# FX-Flash_PLCC_rev_C.net
KiCad netlist of a schematic drawn in EAGLE
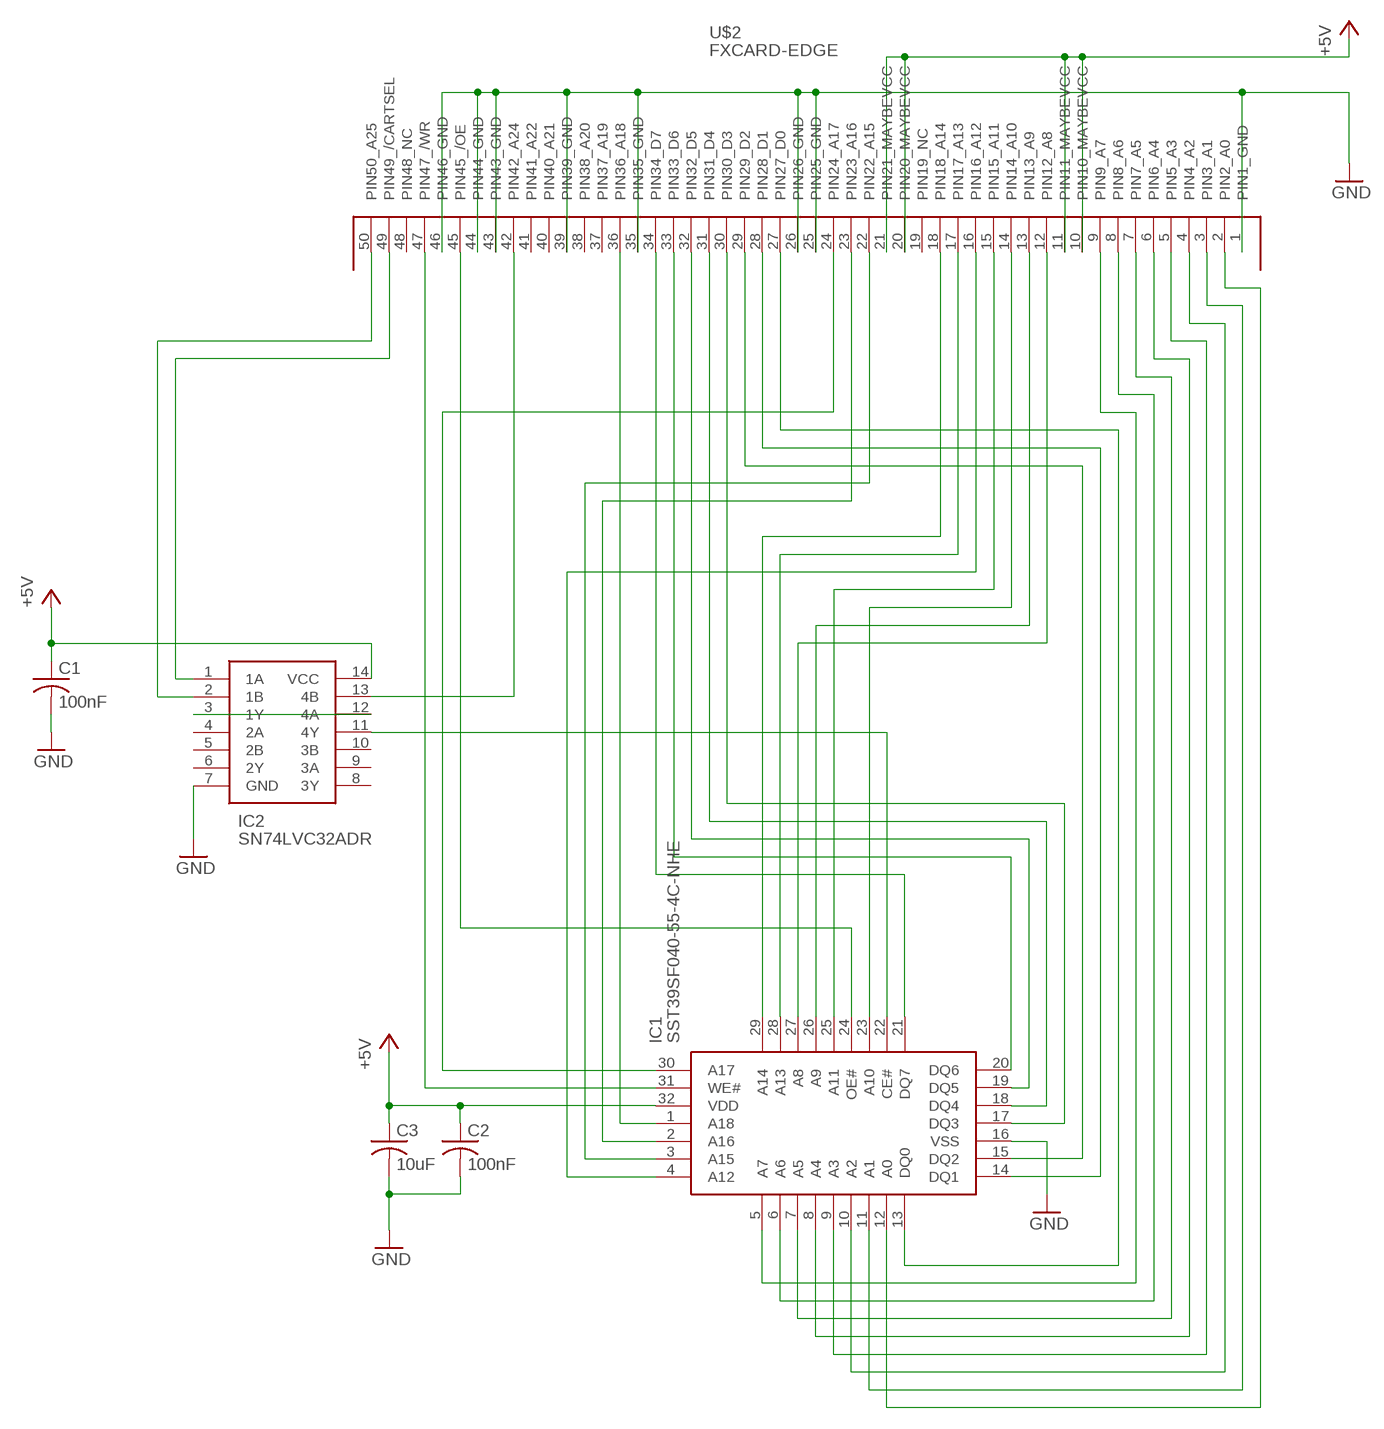
[diagram p0: schematic, sheet 1]

(export (version "E")
  (design (tool "Eeschema 10.0.6"))
  (components
    (comp (ref "C1")
      (value "100nF")
      (footprint "eagle-import:C0805")
      (libsource (lib "eagle-import") (part "C-USC0805"))
    )
    (comp (ref "C2")
      (value "100nF")
      (footprint "eagle-import:C0805")
      (libsource (lib "eagle-import") (part "C-USC0805"))
    )
    (comp (ref "C3")
      (value "10uF")
      (footprint "eagle-import:C0805")
      (libsource (lib "eagle-import") (part "C-USC0805"))
    )
    (comp (ref "IC1")
      (value "SST39SF040-55-4C-NHE")
      (footprint "eagle-import:PLCC127P1245X1499X356-32N")
      (fields (field (name "MOUSER_PART_NUMBER") "579-39SF0405CNHE"))
      (libsource (lib "eagle-import") (part "SST39SF040-55-4C-NHE"))
    )
    (comp (ref "IC2")
      (value "SN74LVC32ADR")
      (footprint "eagle-import:SOIC127P600X175-14N")
      (fields (field (name "MOUSER_PART_NUMBER") "595-SN74LVC32ADR"))
      (libsource (lib "eagle-import") (part "SN74LVC32ADR"))
    )
    (comp (ref "U$2")
      (value "FXCARD-EDGE")
      (footprint "eagle-import:FXCARD-EDGE")
      (libsource (lib "eagle-import") (part "FXCARD-EDGE"))
    )
  )
  (nets
    (net (code "1") (name "+5V") (class "Default")
      (node (ref "C1") (pin "1") (pinfunction "1_1") (pintype "passive"))
      (node (ref "C2") (pin "1") (pinfunction "1_1") (pintype "passive"))
      (node (ref "C3") (pin "1") (pinfunction "1_1") (pintype "passive"))
      (node (ref "IC1") (pin "32") (pinfunction "VDD_32") (pintype "bidirectional"))
      (node (ref "IC2") (pin "14") (pinfunction "VCC_14") (pintype "bidirectional"))
      (node (ref "U$2") (pin "10") (pinfunction "PIN10_MAYBEVCC_10") (pintype "bidirectional"))
      (node (ref "U$2") (pin "11") (pinfunction "PIN11_MAYBEVCC_11") (pintype "bidirectional"))
      (node (ref "U$2") (pin "20") (pinfunction "PIN20_MAYBEVCC_20") (pintype "bidirectional"))
      (node (ref "U$2") (pin "21") (pinfunction "PIN21_MAYBEVCC_21") (pintype "bidirectional"))
    )
    (net (code "2") (name "GND") (class "Default")
      (node (ref "C1") (pin "2") (pinfunction "2_2") (pintype "passive"))
      (node (ref "C2") (pin "2") (pinfunction "2_2") (pintype "passive"))
      (node (ref "C3") (pin "2") (pinfunction "2_2") (pintype "passive"))
      (node (ref "IC1") (pin "16") (pinfunction "VSS_16") (pintype "bidirectional"))
      (node (ref "IC2") (pin "7") (pinfunction "GND_7") (pintype "bidirectional"))
      (node (ref "U$2") (pin "1") (pinfunction "PIN1_GND_1") (pintype "power_in"))
      (node (ref "U$2") (pin "25") (pinfunction "PIN25_GND_25") (pintype "power_in"))
      (node (ref "U$2") (pin "26") (pinfunction "PIN26_GND_26") (pintype "power_in"))
      (node (ref "U$2") (pin "35") (pinfunction "PIN35_GND_35") (pintype "power_in"))
      (node (ref "U$2") (pin "39") (pinfunction "PIN39_GND_39") (pintype "power_in"))
      (node (ref "U$2") (pin "43") (pinfunction "PIN43_GND_43") (pintype "power_in"))
      (node (ref "U$2") (pin "44") (pinfunction "PIN44_GND_44") (pintype "power_in"))
      (node (ref "U$2") (pin "46") (pinfunction "PIN46_GND_46") (pintype "power_in"))
    )
    (net (code "3") (name "Net-(IC1-A0)") (class "Default")
      (node (ref "IC1") (pin "12") (pinfunction "A0_12") (pintype "bidirectional"))
      (node (ref "U$2") (pin "2") (pinfunction "PIN2_A0_2") (pintype "bidirectional"))
    )
    (net (code "4") (name "Net-(IC1-A1)") (class "Default")
      (node (ref "IC1") (pin "11") (pinfunction "A1_11") (pintype "bidirectional"))
      (node (ref "U$2") (pin "3") (pinfunction "PIN3_A1_3") (pintype "bidirectional"))
    )
    (net (code "5") (name "Net-(IC1-A2)") (class "Default")
      (node (ref "IC1") (pin "10") (pinfunction "A2_10") (pintype "bidirectional"))
      (node (ref "U$2") (pin "4") (pinfunction "PIN4_A2_4") (pintype "bidirectional"))
    )
    (net (code "6") (name "Net-(IC1-A3)") (class "Default")
      (node (ref "IC1") (pin "9") (pinfunction "A3_9") (pintype "bidirectional"))
      (node (ref "U$2") (pin "5") (pinfunction "PIN5_A3_5") (pintype "bidirectional"))
    )
    (net (code "7") (name "Net-(IC1-A4)") (class "Default")
      (node (ref "IC1") (pin "8") (pinfunction "A4_8") (pintype "bidirectional"))
      (node (ref "U$2") (pin "6") (pinfunction "PIN6_A4_6") (pintype "bidirectional"))
    )
    (net (code "8") (name "Net-(IC1-A5)") (class "Default")
      (node (ref "IC1") (pin "7") (pinfunction "A5_7") (pintype "bidirectional"))
      (node (ref "U$2") (pin "7") (pinfunction "PIN7_A5_7") (pintype "bidirectional"))
    )
    (net (code "9") (name "Net-(IC1-A6)") (class "Default")
      (node (ref "IC1") (pin "6") (pinfunction "A6_6") (pintype "bidirectional"))
      (node (ref "U$2") (pin "8") (pinfunction "PIN8_A6_8") (pintype "bidirectional"))
    )
    (net (code "10") (name "Net-(IC1-A7)") (class "Default")
      (node (ref "IC1") (pin "5") (pinfunction "A7_5") (pintype "bidirectional"))
      (node (ref "U$2") (pin "9") (pinfunction "PIN9_A7_9") (pintype "bidirectional"))
    )
    (net (code "11") (name "Net-(IC1-A8)") (class "Default")
      (node (ref "IC1") (pin "27") (pinfunction "A8_27") (pintype "bidirectional"))
      (node (ref "U$2") (pin "12") (pinfunction "PIN12_A8_12") (pintype "bidirectional"))
    )
    (net (code "12") (name "Net-(IC1-A9)") (class "Default")
      (node (ref "IC1") (pin "26") (pinfunction "A9_26") (pintype "bidirectional"))
      (node (ref "U$2") (pin "13") (pinfunction "PIN13_A9_13") (pintype "bidirectional"))
    )
    (net (code "13") (name "Net-(IC1-A10)") (class "Default")
      (node (ref "IC1") (pin "23") (pinfunction "A10_23") (pintype "bidirectional"))
      (node (ref "U$2") (pin "14") (pinfunction "PIN14_A10_14") (pintype "bidirectional"))
    )
    (net (code "14") (name "Net-(IC1-A11)") (class "Default")
      (node (ref "IC1") (pin "25") (pinfunction "A11_25") (pintype "bidirectional"))
      (node (ref "U$2") (pin "15") (pinfunction "PIN15_A11_15") (pintype "bidirectional"))
    )
    (net (code "15") (name "Net-(IC1-A12)") (class "Default")
      (node (ref "IC1") (pin "4") (pinfunction "A12_4") (pintype "bidirectional"))
      (node (ref "U$2") (pin "16") (pinfunction "PIN16_A12_16") (pintype "bidirectional"))
    )
    (net (code "16") (name "Net-(IC1-A13)") (class "Default")
      (node (ref "IC1") (pin "28") (pinfunction "A13_28") (pintype "bidirectional"))
      (node (ref "U$2") (pin "17") (pinfunction "PIN17_A13_17") (pintype "bidirectional"))
    )
    (net (code "17") (name "Net-(IC1-A14)") (class "Default")
      (node (ref "IC1") (pin "29") (pinfunction "A14_29") (pintype "bidirectional"))
      (node (ref "U$2") (pin "18") (pinfunction "PIN18_A14_18") (pintype "bidirectional"))
    )
    (net (code "18") (name "Net-(IC1-A15)") (class "Default")
      (node (ref "IC1") (pin "3") (pinfunction "A15_3") (pintype "bidirectional"))
      (node (ref "U$2") (pin "22") (pinfunction "PIN22_A15_22") (pintype "bidirectional"))
    )
    (net (code "19") (name "Net-(IC1-A16)") (class "Default")
      (node (ref "IC1") (pin "2") (pinfunction "A16_2") (pintype "bidirectional"))
      (node (ref "U$2") (pin "23") (pinfunction "PIN23_A16_23") (pintype "bidirectional"))
    )
    (net (code "20") (name "Net-(IC1-A17)") (class "Default")
      (node (ref "IC1") (pin "30") (pinfunction "A17_30") (pintype "bidirectional"))
      (node (ref "U$2") (pin "24") (pinfunction "PIN24_A17_24") (pintype "bidirectional"))
    )
    (net (code "21") (name "Net-(IC1-A18)") (class "Default")
      (node (ref "IC1") (pin "1") (pinfunction "A18_1") (pintype "bidirectional"))
      (node (ref "U$2") (pin "36") (pinfunction "PIN36_A18_36") (pintype "bidirectional"))
    )
    (net (code "22") (name "Net-(IC1-CE#)") (class "Default")
      (node (ref "IC1") (pin "22") (pinfunction "CE#_22") (pintype "bidirectional"))
      (node (ref "IC2") (pin "11") (pinfunction "4Y_11") (pintype "bidirectional"))
    )
    (net (code "23") (name "Net-(IC1-DQ0)") (class "Default")
      (node (ref "IC1") (pin "13") (pinfunction "DQ0_13") (pintype "bidirectional"))
      (node (ref "U$2") (pin "27") (pinfunction "PIN27_D0_27") (pintype "bidirectional"))
    )
    (net (code "24") (name "Net-(IC1-DQ1)") (class "Default")
      (node (ref "IC1") (pin "14") (pinfunction "DQ1_14") (pintype "bidirectional"))
      (node (ref "U$2") (pin "28") (pinfunction "PIN28_D1_28") (pintype "bidirectional"))
    )
    (net (code "25") (name "Net-(IC1-DQ2)") (class "Default")
      (node (ref "IC1") (pin "15") (pinfunction "DQ2_15") (pintype "bidirectional"))
      (node (ref "U$2") (pin "29") (pinfunction "PIN29_D2_29") (pintype "bidirectional"))
    )
    (net (code "26") (name "Net-(IC1-DQ3)") (class "Default")
      (node (ref "IC1") (pin "17") (pinfunction "DQ3_17") (pintype "bidirectional"))
      (node (ref "U$2") (pin "30") (pinfunction "PIN30_D3_30") (pintype "bidirectional"))
    )
    (net (code "27") (name "Net-(IC1-DQ4)") (class "Default")
      (node (ref "IC1") (pin "18") (pinfunction "DQ4_18") (pintype "bidirectional"))
      (node (ref "U$2") (pin "31") (pinfunction "PIN31_D4_31") (pintype "bidirectional"))
    )
    (net (code "28") (name "Net-(IC1-DQ5)") (class "Default")
      (node (ref "IC1") (pin "19") (pinfunction "DQ5_19") (pintype "bidirectional"))
      (node (ref "U$2") (pin "32") (pinfunction "PIN32_D5_32") (pintype "bidirectional"))
    )
    (net (code "29") (name "Net-(IC1-DQ6)") (class "Default")
      (node (ref "IC1") (pin "20") (pinfunction "DQ6_20") (pintype "bidirectional"))
      (node (ref "U$2") (pin "33") (pinfunction "PIN33_D6_33") (pintype "bidirectional"))
    )
    (net (code "30") (name "Net-(IC1-DQ7)") (class "Default")
      (node (ref "IC1") (pin "21") (pinfunction "DQ7_21") (pintype "bidirectional"))
      (node (ref "U$2") (pin "34") (pinfunction "PIN34_D7_34") (pintype "bidirectional"))
    )
    (net (code "31") (name "Net-(IC1-OE#)") (class "Default")
      (node (ref "IC1") (pin "24") (pinfunction "OE#_24") (pintype "bidirectional"))
      (node (ref "U$2") (pin "45") (pinfunction "PIN45_/OE_45") (pintype "bidirectional"))
    )
    (net (code "32") (name "Net-(IC1-WE#)") (class "Default")
      (node (ref "IC1") (pin "31") (pinfunction "WE#_31") (pintype "bidirectional"))
      (node (ref "U$2") (pin "47") (pinfunction "PIN47_/WR_47") (pintype "bidirectional"))
    )
    (net (code "33") (name "Net-(IC2-1A)") (class "Default")
      (node (ref "IC2") (pin "1") (pinfunction "1A_1") (pintype "bidirectional"))
      (node (ref "U$2") (pin "49") (pinfunction "PIN49_/CARTSEL_49") (pintype "bidirectional"))
    )
    (net (code "34") (name "Net-(IC2-1B)") (class "Default")
      (node (ref "IC2") (pin "2") (pinfunction "1B_2") (pintype "bidirectional"))
      (node (ref "U$2") (pin "50") (pinfunction "PIN50_A25_50") (pintype "bidirectional"))
    )
    (net (code "35") (name "Net-(IC2-1Y)") (class "Default")
      (node (ref "IC2") (pin "12") (pinfunction "4A_12") (pintype "bidirectional"))
      (node (ref "IC2") (pin "3") (pinfunction "1Y_3") (pintype "bidirectional"))
    )
    (net (code "36") (name "Net-(IC2-4B)") (class "Default")
      (node (ref "IC2") (pin "13") (pinfunction "4B_13") (pintype "bidirectional"))
      (node (ref "U$2") (pin "42") (pinfunction "PIN42_A24_42") (pintype "bidirectional"))
    )
    (net (code "37") (name "unconnected-(IC2-2A-Pad4)") (class "Default")
      (node (ref "IC2") (pin "4") (pinfunction "2A_4") (pintype "bidirectional"))
    )
    (net (code "38") (name "unconnected-(IC2-2B-Pad5)") (class "Default")
      (node (ref "IC2") (pin "5") (pinfunction "2B_5") (pintype "bidirectional"))
    )
    (net (code "39") (name "unconnected-(IC2-2Y-Pad6)") (class "Default")
      (node (ref "IC2") (pin "6") (pinfunction "2Y_6") (pintype "bidirectional"))
    )
    (net (code "40") (name "unconnected-(IC2-3A-Pad9)") (class "Default")
      (node (ref "IC2") (pin "9") (pinfunction "3A_9") (pintype "bidirectional"))
    )
    (net (code "41") (name "unconnected-(IC2-3B-Pad10)") (class "Default")
      (node (ref "IC2") (pin "10") (pinfunction "3B_10") (pintype "bidirectional"))
    )
    (net (code "42") (name "unconnected-(IC2-3Y-Pad8)") (class "Default")
      (node (ref "IC2") (pin "8") (pinfunction "3Y_8") (pintype "bidirectional"))
    )
    (net (code "43") (name "unconnected-(U$2-PIN19_NC-Pad19)") (class "Default")
      (node (ref "U$2") (pin "19") (pinfunction "PIN19_NC_19") (pintype "bidirectional"))
    )
    (net (code "44") (name "unconnected-(U$2-PIN37_A19-Pad37)") (class "Default")
      (node (ref "U$2") (pin "37") (pinfunction "PIN37_A19_37") (pintype "bidirectional"))
    )
    (net (code "45") (name "unconnected-(U$2-PIN38_A20-Pad38)") (class "Default")
      (node (ref "U$2") (pin "38") (pinfunction "PIN38_A20_38") (pintype "bidirectional"))
    )
    (net (code "46") (name "unconnected-(U$2-PIN40_A21-Pad40)") (class "Default")
      (node (ref "U$2") (pin "40") (pinfunction "PIN40_A21_40") (pintype "bidirectional"))
    )
    (net (code "47") (name "unconnected-(U$2-PIN41_A22-Pad41)") (class "Default")
      (node (ref "U$2") (pin "41") (pinfunction "PIN41_A22_41") (pintype "bidirectional"))
    )
    (net (code "48") (name "unconnected-(U$2-PIN48_NC-Pad48)") (class "Default")
      (node (ref "U$2") (pin "48") (pinfunction "PIN48_NC_48") (pintype "bidirectional"))
    )
  )
)
